# EEU_SEH.net
KiCad netlist of a schematic drawn in Altium Designer
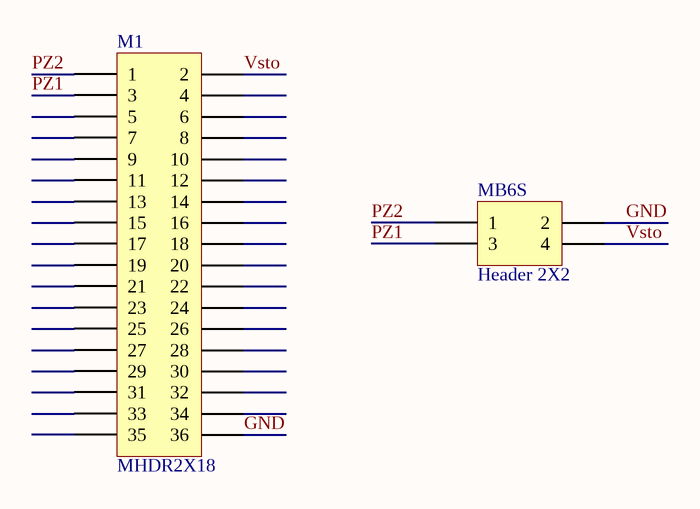
[diagram p0: EEU_SEH.SchDoc]

(export (version "E")
  (design (tool "Eeschema 10.0.6"))
  (components
    (comp (ref "M1")
      (value "MHDR2X18")
      (footprint "module9x4")
      (description "Header, 18-Pin, Dual row")
      (fields (field (name "PUBLISHER") "Altium Limited"))
      (libsource (lib "Miscellaneous Connectors") (part "MHDR2X18"))
    )
    (comp (ref "MB6S")
      (value "Header 2X2")
      (footprint "MB6S")
      (description "Header, 2-Pin, Dual row")
      (fields (field (name "PUBLISHER") "Altium Limited"))
      (libsource (lib "Miscellaneous Connectors") (part "Header 2X2"))
    )
  )
  (nets
    (net (code "1") (name "/GND") (class "Default")
      (node (ref "M1") (pin "36") (pinfunction "36_36") (pintype "passive"))
      (node (ref "MB6S") (pin "2") (pinfunction "2_2") (pintype "passive"))
    )
    (net (code "2") (name "/PZ1") (class "Default")
      (node (ref "M1") (pin "3") (pinfunction "3_3") (pintype "passive"))
      (node (ref "MB6S") (pin "3") (pinfunction "3_3") (pintype "passive"))
    )
    (net (code "3") (name "/PZ2") (class "Default")
      (node (ref "M1") (pin "1") (pinfunction "1_1") (pintype "passive"))
      (node (ref "MB6S") (pin "1") (pinfunction "1_1") (pintype "passive"))
    )
    (net (code "4") (name "/Vsto") (class "Default")
      (node (ref "M1") (pin "2") (pinfunction "2_2") (pintype "passive"))
      (node (ref "MB6S") (pin "4") (pinfunction "4_4") (pintype "passive"))
    )
    (net (code "5") (name "unconnected-(M1-Pad4)") (class "Default")
      (node (ref "M1") (pin "4") (pinfunction "4_4") (pintype "passive"))
    )
    (net (code "6") (name "unconnected-(M1-Pad5)") (class "Default")
      (node (ref "M1") (pin "5") (pinfunction "5_5") (pintype "passive"))
    )
    (net (code "7") (name "unconnected-(M1-Pad6)") (class "Default")
      (node (ref "M1") (pin "6") (pinfunction "6_6") (pintype "passive"))
    )
    (net (code "8") (name "unconnected-(M1-Pad7)") (class "Default")
      (node (ref "M1") (pin "7") (pinfunction "7_7") (pintype "passive"))
    )
    (net (code "9") (name "unconnected-(M1-Pad8)") (class "Default")
      (node (ref "M1") (pin "8") (pinfunction "8_8") (pintype "passive"))
    )
    (net (code "10") (name "unconnected-(M1-Pad9)") (class "Default")
      (node (ref "M1") (pin "9") (pinfunction "9_9") (pintype "passive"))
    )
    (net (code "11") (name "unconnected-(M1-Pad10)") (class "Default")
      (node (ref "M1") (pin "10") (pinfunction "10_10") (pintype "passive"))
    )
    (net (code "12") (name "unconnected-(M1-Pad11)") (class "Default")
      (node (ref "M1") (pin "11") (pinfunction "11_11") (pintype "passive"))
    )
    (net (code "13") (name "unconnected-(M1-Pad12)") (class "Default")
      (node (ref "M1") (pin "12") (pinfunction "12_12") (pintype "passive"))
    )
    (net (code "14") (name "unconnected-(M1-Pad13)") (class "Default")
      (node (ref "M1") (pin "13") (pinfunction "13_13") (pintype "passive"))
    )
    (net (code "15") (name "unconnected-(M1-Pad14)") (class "Default")
      (node (ref "M1") (pin "14") (pinfunction "14_14") (pintype "passive"))
    )
    (net (code "16") (name "unconnected-(M1-Pad15)") (class "Default")
      (node (ref "M1") (pin "15") (pinfunction "15_15") (pintype "passive"))
    )
    (net (code "17") (name "unconnected-(M1-Pad16)") (class "Default")
      (node (ref "M1") (pin "16") (pinfunction "16_16") (pintype "passive"))
    )
    (net (code "18") (name "unconnected-(M1-Pad17)") (class "Default")
      (node (ref "M1") (pin "17") (pinfunction "17_17") (pintype "passive"))
    )
    (net (code "19") (name "unconnected-(M1-Pad18)") (class "Default")
      (node (ref "M1") (pin "18") (pinfunction "18_18") (pintype "passive"))
    )
    (net (code "20") (name "unconnected-(M1-Pad19)") (class "Default")
      (node (ref "M1") (pin "19") (pinfunction "19_19") (pintype "passive"))
    )
    (net (code "21") (name "unconnected-(M1-Pad20)") (class "Default")
      (node (ref "M1") (pin "20") (pinfunction "20_20") (pintype "passive"))
    )
    (net (code "22") (name "unconnected-(M1-Pad21)") (class "Default")
      (node (ref "M1") (pin "21") (pinfunction "21_21") (pintype "passive"))
    )
    (net (code "23") (name "unconnected-(M1-Pad22)") (class "Default")
      (node (ref "M1") (pin "22") (pinfunction "22_22") (pintype "passive"))
    )
    (net (code "24") (name "unconnected-(M1-Pad23)") (class "Default")
      (node (ref "M1") (pin "23") (pinfunction "23_23") (pintype "passive"))
    )
    (net (code "25") (name "unconnected-(M1-Pad24)") (class "Default")
      (node (ref "M1") (pin "24") (pinfunction "24_24") (pintype "passive"))
    )
    (net (code "26") (name "unconnected-(M1-Pad25)") (class "Default")
      (node (ref "M1") (pin "25") (pinfunction "25_25") (pintype "passive"))
    )
    (net (code "27") (name "unconnected-(M1-Pad26)") (class "Default")
      (node (ref "M1") (pin "26") (pinfunction "26_26") (pintype "passive"))
    )
    (net (code "28") (name "unconnected-(M1-Pad27)") (class "Default")
      (node (ref "M1") (pin "27") (pinfunction "27_27") (pintype "passive"))
    )
    (net (code "29") (name "unconnected-(M1-Pad28)") (class "Default")
      (node (ref "M1") (pin "28") (pinfunction "28_28") (pintype "passive"))
    )
    (net (code "30") (name "unconnected-(M1-Pad29)") (class "Default")
      (node (ref "M1") (pin "29") (pinfunction "29_29") (pintype "passive"))
    )
    (net (code "31") (name "unconnected-(M1-Pad30)") (class "Default")
      (node (ref "M1") (pin "30") (pinfunction "30_30") (pintype "passive"))
    )
    (net (code "32") (name "unconnected-(M1-Pad31)") (class "Default")
      (node (ref "M1") (pin "31") (pinfunction "31_31") (pintype "passive"))
    )
    (net (code "33") (name "unconnected-(M1-Pad32)") (class "Default")
      (node (ref "M1") (pin "32") (pinfunction "32_32") (pintype "passive"))
    )
    (net (code "34") (name "unconnected-(M1-Pad33)") (class "Default")
      (node (ref "M1") (pin "33") (pinfunction "33_33") (pintype "passive"))
    )
    (net (code "35") (name "unconnected-(M1-Pad34)") (class "Default")
      (node (ref "M1") (pin "34") (pinfunction "34_34") (pintype "passive"))
    )
    (net (code "36") (name "unconnected-(M1-Pad35)") (class "Default")
      (node (ref "M1") (pin "35") (pinfunction "35_35") (pintype "passive"))
    )
  )
)
